# hot-wand-lite.net
KiCad netlist of a schematic drawn in EAGLE
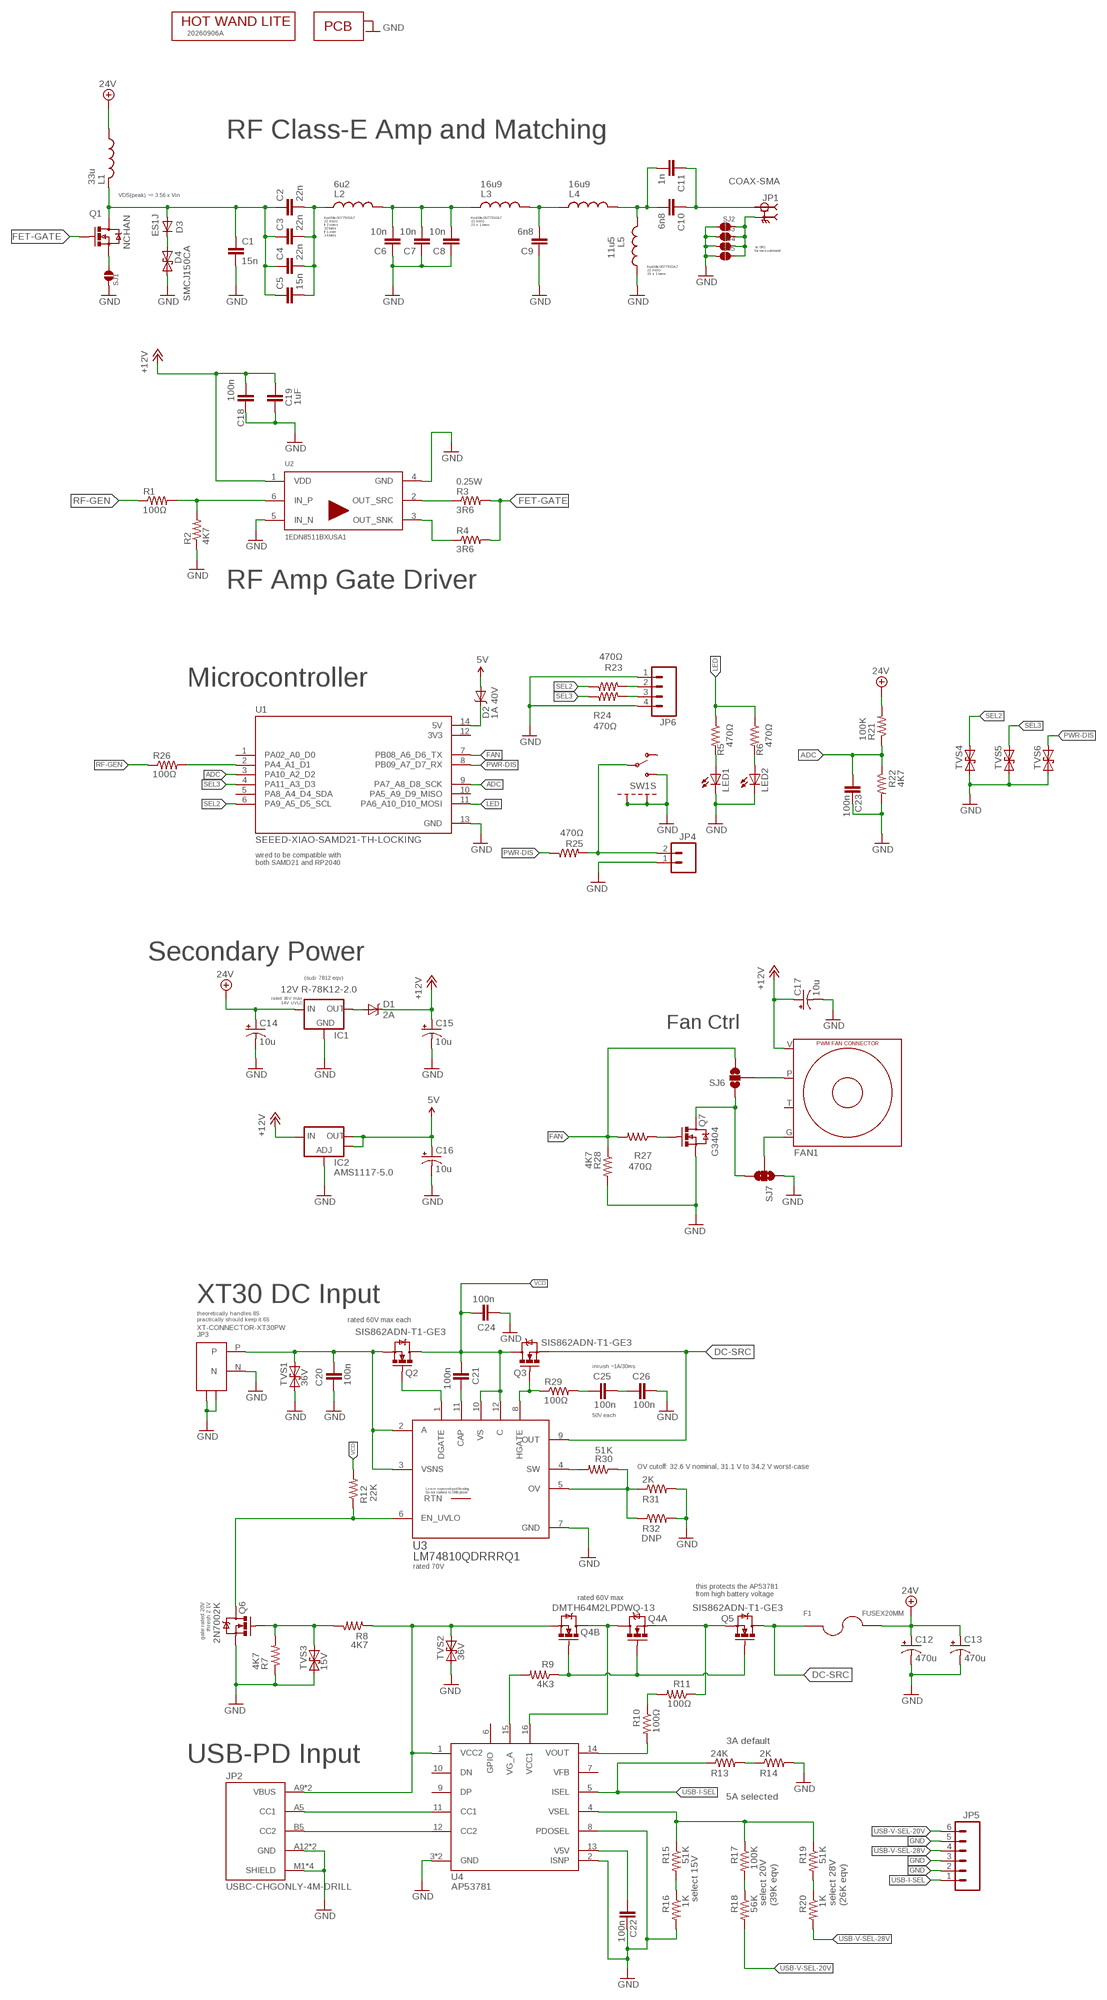
[diagram p0: schematic, sheet 1]

(export (version "E")
  (design (tool "Eeschema 10.0.6"))
  (components
    (comp (ref "C1")
      (value "15n")
      (footprint "eagle-import:1206")
      (fields (field (name "JLCPARTNUM") "C3858208") (field (name "PARTNUM") "C3216C0G2E153J160AA"))
      (libsource (lib "eagle-import") (part "CAP1206"))
    )
    (comp (ref "C2")
      (value "22n")
      (footprint "eagle-import:1206")
      (fields (field (name "JLCPARTNUM") "C3862155"))
      (libsource (lib "eagle-import") (part "CAP1206"))
    )
    (comp (ref "C3")
      (value "22n")
      (footprint "eagle-import:1206")
      (fields (field (name "JLCPARTNUM") "C3862155"))
      (libsource (lib "eagle-import") (part "CAP1206"))
    )
    (comp (ref "C4")
      (value "22n")
      (footprint "eagle-import:1206")
      (fields (field (name "JLCPARTNUM") "C3862155") (field (name "PARTNUM") "GCM31C5C2E223JX03L"))
      (libsource (lib "eagle-import") (part "CAP1206"))
    )
    (comp (ref "C5")
      (value "15n")
      (footprint "eagle-import:1206")
      (fields (field (name "JLCPARTNUM") "C3858208") (field (name "PARTNUM") "C3216C0G2E153J160AA"))
      (libsource (lib "eagle-import") (part "CAP1206"))
    )
    (comp (ref "C6")
      (value "10n")
      (footprint "eagle-import:1206")
      (fields
        (field (name "JLCPARTNUM") "C2261646;C2170837;C2175075")
        (field (name "PARTNUM") "C3216C0G2E103J115AA")
      )
      (libsource (lib "eagle-import") (part "CAP1206"))
    )
    (comp (ref "C7")
      (value "10n")
      (footprint "eagle-import:1206")
      (fields (field (name "JLCPARTNUM") "C2261646") (field (name "PARTNUM") "GRM31B5C2E103JWA1L"))
      (libsource (lib "eagle-import") (part "CAP1206"))
    )
    (comp (ref "C8")
      (value "10n")
      (footprint "eagle-import:1206")
      (fields (field (name "JLCPARTNUM") "C2261646") (field (name "PARTNUM") "GRM31B5C2E103JWA1L"))
      (libsource (lib "eagle-import") (part "CAP1206"))
    )
    (comp (ref "C9")
      (value "6n8")
      (footprint "eagle-import:1206")
      (fields (field (name "JLCPARTNUM") "C2182121") (field (name "PARTNUM") "C1206C682JCGACAUTO"))
      (libsource (lib "eagle-import") (part "CAP1206"))
    )
    (comp (ref "C10")
      (value "6n8")
      (footprint "eagle-import:1206")
      (fields (field (name "JLCPARTNUM") "C2182121") (field (name "PARTNUM") "C1206C682JCGACAUTO"))
      (libsource (lib "eagle-import") (part "CAP1206"))
    )
    (comp (ref "C11")
      (value "1n")
      (footprint "eagle-import:1206")
      (fields (field (name "JLCPARTNUM") "C3859218") (field (name "PARTNUM") "GCM31C5C3A102FX03L"))
      (libsource (lib "eagle-import") (part "CAP1206"))
    )
    (comp (ref "C12")
      (value "470u")
      (footprint "eagle-import:CPOL-RADIAL-COMBO-10MM")
      (fields (field (name "PARTNUM") "UHW1H471MPD"))
      (libsource (lib "eagle-import") (part "CAP_POLPTH5"))
    )
    (comp (ref "C13")
      (value "470u")
      (footprint "eagle-import:CPOL-RADIAL-COMBO-10MM")
      (fields (field (name "PARTNUM") "UHW1H471MPD"))
      (libsource (lib "eagle-import") (part "CAP_POLPTH5"))
    )
    (comp (ref "C14")
      (value "10u")
      (footprint "eagle-import:EIA3216-KIT")
      (fields
        (field (name "JLCPARTNUM") "C13585")
        (field (name "PARTNUM") "MLASU31LBB5106KTNA01;GRT31CR61H106KE01K")
      )
      (libsource (lib "eagle-import") (part "CAP_POL1206-KIT"))
    )
    (comp (ref "C15")
      (value "10u")
      (footprint "eagle-import:EIA3216-KIT")
      (fields (field (name "JLCPARTNUM") "C13585") (field (name "PARTNUM") "TAJA106K016TNJ;T491A106K016AT"))
      (libsource (lib "eagle-import") (part "CAP_POL1206-KIT"))
    )
    (comp (ref "C16")
      (value "10u")
      (footprint "eagle-import:EIA3216-KIT")
      (fields (field (name "JLCPARTNUM") "C13585") (field (name "PARTNUM") "TAJA106K016TNJ;T491A106K016AT"))
      (libsource (lib "eagle-import") (part "CAP_POL1206-KIT"))
    )
    (comp (ref "C17")
      (value "10u")
      (footprint "eagle-import:EIA3216-KIT")
      (fields
        (field (name "JLCPARTNUM") "C13585")
        (field (name "PARTNUM") "MLASU31LBB5106KTNA01;GRT31CR61H106KE01K")
      )
      (libsource (lib "eagle-import") (part "CAP_POL1206-KIT"))
    )
    (comp (ref "C18")
      (value "100n")
      (footprint "eagle-import:0603-CAP")
      (fields (field (name "JLCPARTNUM") "C14663"))
      (libsource (lib "eagle-import") (part "CAP0603-CAP"))
    )
    (comp (ref "C19")
      (value "1uF")
      (footprint "eagle-import:0603-CAP")
      (fields (field (name "JLCPARTNUM") "C15849"))
      (libsource (lib "eagle-import") (part "CAP0603-CAP"))
    )
    (comp (ref "C20")
      (value "100n")
      (footprint "eagle-import:0603-CAP")
      (fields (field (name "JLCPARTNUM") "C14663"))
      (libsource (lib "eagle-import") (part "CAP0603-CAP"))
    )
    (comp (ref "C21")
      (value "100n")
      (footprint "eagle-import:0603-CAP")
      (fields (field (name "JLCPARTNUM") "C14663"))
      (libsource (lib "eagle-import") (part "CAP0603-CAP"))
    )
    (comp (ref "C22")
      (value "100n")
      (footprint "eagle-import:0603-CAP")
      (fields (field (name "JLCPARTNUM") "C14663"))
      (libsource (lib "eagle-import") (part "CAP0603-CAP"))
    )
    (comp (ref "C23")
      (value "100n")
      (footprint "eagle-import:0603-CAP")
      (fields (field (name "JLCPARTNUM") "C14663"))
      (libsource (lib "eagle-import") (part "CAP0603-CAP"))
    )
    (comp (ref "C24")
      (value "100n")
      (footprint "eagle-import:0603-CAP")
      (fields (field (name "JLCPARTNUM") "C14663"))
      (libsource (lib "eagle-import") (part "CAP0603-CAP"))
    )
    (comp (ref "C25")
      (value "100n")
      (footprint "eagle-import:0603-CAP")
      (fields (field (name "JLCPARTNUM") "C14663"))
      (libsource (lib "eagle-import") (part "CAP0603-CAP"))
    )
    (comp (ref "C26")
      (value "100n")
      (footprint "eagle-import:0603-CAP")
      (fields (field (name "JLCPARTNUM") "C14663"))
      (libsource (lib "eagle-import") (part "CAP0603-CAP"))
    )
    (comp (ref "D1")
      (value "2A")
      (footprint "eagle-import:SMA-DIODE")
      (fields (field (name "JLCPARTNUM") "C698873") (field (name "PARTNUM") "VSSAF5N50;SL36A"))
      (libsource (lib "eagle-import") (part "DIODE-SCHOTTKY_"))
    )
    (comp (ref "D2")
      (value "1A 40V")
      (footprint "eagle-import:SOD123FL")
      (fields (field (name "JLCPARTNUM") "C8598"))
      (libsource (lib "eagle-import") (part "DIODE-SCHOTTKYSOD123FL"))
    )
    (comp (ref "D3")
      (value "ES1J")
      (footprint "eagle-import:SMA-DIODE")
      (fields (field (name "JLCPARTNUM") "C64879"))
      (libsource (lib "eagle-import") (part "DIODESMA"))
    )
    (comp (ref "D4")
      (value "SMCJ150CA")
      (footprint "eagle-import:SMC")
      (fields (field (name "JLCPARTNUM") "C2649864"))
      (libsource (lib "eagle-import") (part "TVSSMC"))
    )
    (comp (ref "F1")
      (value "FUSEX20MM")
      (footprint "eagle-import:FUSE_5MM")
      (fields (field (name "PARTNUM") "3518P"))
      (libsource (lib "eagle-import") (part "FUSEX20MM"))
    )
    (comp (ref "FAN1")
      (value "FAN-CONN-X4-CONN-X4")
      (footprint "eagle-import:FAN-CONN-X4")
      (fields (field (name "PARTNUM") "0470531000"))
      (libsource (lib "eagle-import") (part "FAN-CONN-X4-CONN-X4"))
    )
    (comp (ref "IC1")
      (value "12V R-78K12-2.0")
      (footprint "eagle-import:TO220-BUCK-12V")
      (fields (field (name "JLC-DNP") "1") (field (name "PARTNUM") "R-78K12-2.0"))
      (libsource (lib "eagle-import") (part "V_REG_78XX-BUCK"))
    )
    (comp (ref "IC2")
      (value "AMS1117-5.0")
      (footprint "eagle-import:SOT223")
      (fields (field (name "JLCPARTNUM") "C6187"))
      (libsource (lib "eagle-import") (part "V_REG_LM1117SOT223"))
    )
    (comp (ref "JP1")
      (value "COAX-SMA")
      (footprint "eagle-import:SAMTEC_SMA-J-P-H-ST-EM1-LGRPAD")
      (fields (field (name "MF") "Samtec") (field (name "MP") "SMA-J-P-H-ST-EM1"))
      (libsource (lib "eagle-import") (part "COAX-SMA-EDGE-LGRPAD"))
    )
    (comp (ref "JP2")
      (value "USBC-CHGONLY-4M-DRILL")
      (footprint "eagle-import:SAMESKY_UJC-H-G-SMT-2-P6-TR-DRILL")
      (fields
        (field (name "DIGIKEY_PART_NUMBER") "2223-UJC-H-G-SMT-2-P6-TRCT-ND")
        (field (name "MF") "Same Sky")
        (field (name "MP") "UJC-H-G-SMT-2-P6-TR")
        (field (name "JLC-DNP") "1")
        (field (name "PARTNUM") "UJC-H-G-SMT-P6-TR")
      )
      (libsource (lib "eagle-import") (part "USBC-CHGONLY-4M-DRILL"))
    )
    (comp (ref "JP3")
      (value "XT-CONNECTOR-XT30PW")
      (footprint "eagle-import:XT30PW")
      (fields (field (name "JLC-DNP") "1") (field (name "PARTNUM") "XT30PW-M"))
      (libsource (lib "eagle-import") (part "XT-CONNECTOR-XT30PW"))
    )
    (comp (ref "JP4")
      (value "M02PTH3")
      (footprint "eagle-import:1X02_LONGPADS")
      (libsource (lib "eagle-import") (part "M02PTH3"))
    )
    (comp (ref "JP5")
      (value "M06LOCK")
      (footprint "eagle-import:1X06_LOCK")
      (libsource (lib "eagle-import") (part "M06LOCK"))
    )
    (comp (ref "JP6")
      (value "M04LOCK")
      (footprint "eagle-import:1X04_LOCK")
      (libsource (lib "eagle-import") (part "M04LOCK"))
    )
    (comp (ref "L1")
      (value "33u")
      (footprint "eagle-import:IND_SRP1265A")
      (fields
        (field (name "JLCPARTNUM") "C2453886")
        (field (name "PARTNUM") "PA4343.333NLT;SRP1265A-330M;SRP1265CC-330M")
      )
      (libsource (lib "eagle-import") (part "INDUCTOR-SRP1265A"))
    )
    (comp (ref "L2")
      (value "6u2")
      (footprint "eagle-import:IND-KOOLMU-2W")
      (libsource (lib "eagle-import") (part "INDUCTOR-KOOLMU-2W"))
    )
    (comp (ref "L3")
      (value "16u9")
      (footprint "eagle-import:IND-KOOLMU")
      (libsource (lib "eagle-import") (part "INDUCTOR-KOOLMU"))
    )
    (comp (ref "L4")
      (value "16u9")
      (footprint "eagle-import:IND-KOOLMU")
      (libsource (lib "eagle-import") (part "INDUCTOR-KOOLMU"))
    )
    (comp (ref "L5")
      (value "11u5")
      (footprint "eagle-import:IND-KOOLMU")
      (libsource (lib "eagle-import") (part "INDUCTOR-KOOLMU"))
    )
    (comp (ref "LED1")
      (value "LED")
      (footprint "eagle-import:LED_LTST-S220KRKT")
      (fields (field (name "JLCPARTNUM") "C284935") (field (name "PARTNUM") "LTST-S220KRKT"))
      (libsource (lib "eagle-import") (part "LED-LTST-S220KRKT"))
    )
    (comp (ref "LED2")
      (value "LED")
      (footprint "eagle-import:LED-0603")
      (fields (field (name "JLC-DNP") "1"))
      (libsource (lib "eagle-import") (part "LED0603"))
    )
    (comp (ref "PCB1")
      (value "PCB-OUTLINE")
      (footprint "eagle-import:PCB-OUTLINE")
      (fields (field (name "JLC-DNP") "1"))
      (libsource (lib "eagle-import") (part "PCB-OUTLINE"))
    )
    (comp (ref "PCB2")
      (value "PCB-ART-VER-LITE")
      (footprint "eagle-import:PCB-ART-VERSION-LITE")
      (libsource (lib "eagle-import") (part "PCB-ART-VER-LITE"))
    )
    (comp (ref "Q1")
      (value "NCHAN")
      (footprint "eagle-import:TO247-COMBO")
      (libsource (lib "eagle-import") (part "MOSFET-NCHANNEL-TO247-COMBO"))
    )
    (comp (ref "Q2")
      (value "SIS862ADN-T1-GE3")
      (footprint "eagle-import:POWERPAK-1212-8")
      (fields (field (name "PARTNUM") "SIS862ADN-T1-GE3"))
      (libsource (lib "eagle-import") (part "MOSFET-NCHANNEL-POWERPAK1212-8"))
    )
    (comp (ref "Q3")
      (value "SIS862ADN-T1-GE3")
      (footprint "eagle-import:POWERPAK-1212-8")
      (fields (field (name "PARTNUM") "SIS862ADN-T1-GE3"))
      (libsource (lib "eagle-import") (part "MOSFET-NCHANNEL-POWERPAK1212-8"))
    )
    (comp (ref "Q4")
      (value "DMTH64M2LPDWQ-13")
      (footprint "eagle-import:POWERPAK-SO8-X2")
      (fields (field (name "JLC-DNP") "1") (field (name "PARTNUM") "DMTH64M2LPDWQ-13"))
      (libsource (lib "eagle-import") (part "MOSFET-NCHAN-X2-PPSO8X2"))
    )
    (comp (ref "Q5")
      (value "SIS862ADN-T1-GE3")
      (footprint "eagle-import:POWERPAK-1212-8")
      (fields (field (name "JLC-DNP") "1") (field (name "PARTNUM") "SIS862ADN-T1-GE3"))
      (libsource (lib "eagle-import") (part "MOSFET-NCHANNEL-POWERPAK1212-8"))
    )
    (comp (ref "Q6")
      (value "2N7002K")
      (footprint "eagle-import:SOT23-3")
      (fields
        (field (name "JLCPARTNUM") "C14498;C547263;C5224211;C54347659")
        (field (name "PARTNUM") "2N7002K;SSM3K388R,LF;Si2318CDS-T1-GE3;PMV60ENEAR")
      )
      (libsource (lib "eagle-import") (part "MOSFET-NCHANNELSMD"))
    )
    (comp (ref "Q7")
      (value "G3404")
      (footprint "eagle-import:SOT23-3")
      (fields
        (field (name "JLCPARTNUM") "C14498;C547263;C96615")
        (field (name "PARTNUM") "G3404;MMFTN3404A;PJA3404A;Si2318CDS-T1-GE3;PMV60ENEAR")
      )
      (libsource (lib "eagle-import") (part "MOSFET-NCHANNELSMD"))
    )
    (comp (ref "R1")
      (value "100Ω")
      (footprint "eagle-import:0805")
      (fields (field (name "JLCPARTNUM") "C441975"))
      (libsource (lib "eagle-import") (part "RESISTOR0805-RES"))
    )
    (comp (ref "R2")
      (value "4K7")
      (footprint "eagle-import:0603-RES")
      (fields (field (name "JLCPARTNUM") "C23162"))
      (libsource (lib "eagle-import") (part "RESISTOR0603-RES"))
    )
    (comp (ref "R3")
      (value "3R6")
      (footprint "eagle-import:0603-RES")
      (fields (field (name "JLCPARTNUM") "C445783"))
      (libsource (lib "eagle-import") (part "RESISTOR0603-RES"))
    )
    (comp (ref "R4")
      (value "3R6")
      (footprint "eagle-import:0603-RES")
      (fields (field (name "JLCPARTNUM") "C445783"))
      (libsource (lib "eagle-import") (part "RESISTOR0603-RES"))
    )
    (comp (ref "R5")
      (value "470Ω")
      (footprint "eagle-import:0603-RES")
      (fields (field (name "JLCPARTNUM") "C23179"))
      (libsource (lib "eagle-import") (part "RESISTOR0603-RES"))
    )
    (comp (ref "R6")
      (value "470Ω")
      (footprint "eagle-import:0603-RES")
      (fields (field (name "JLCPARTNUM") "C23179"))
      (libsource (lib "eagle-import") (part "RESISTOR0603-RES"))
    )
    (comp (ref "R7")
      (value "4K7")
      (footprint "eagle-import:0603-RES")
      (fields (field (name "JLCPARTNUM") "C23162"))
      (libsource (lib "eagle-import") (part "RESISTOR0603-RES"))
    )
    (comp (ref "R8")
      (value "4K7")
      (footprint "eagle-import:0603-RES")
      (fields (field (name "JLCPARTNUM") "C23162"))
      (libsource (lib "eagle-import") (part "RESISTOR0603-RES"))
    )
    (comp (ref "R9")
      (value "4K3")
      (footprint "eagle-import:0603-RES")
      (fields (field (name "JLCPARTNUM") "C23159"))
      (libsource (lib "eagle-import") (part "RESISTOR0603-RES"))
    )
    (comp (ref "R10")
      (value "100Ω")
      (footprint "eagle-import:0805")
      (fields (field (name "JLCPARTNUM") "C441975"))
      (libsource (lib "eagle-import") (part "RESISTOR0805-RES"))
    )
    (comp (ref "R11")
      (value "100Ω")
      (footprint "eagle-import:0805")
      (fields (field (name "JLCPARTNUM") "C441975"))
      (libsource (lib "eagle-import") (part "RESISTOR0805-RES"))
    )
    (comp (ref "R12")
      (value "22K")
      (footprint "eagle-import:0603-RES")
      (fields (field (name "JLCPARTNUM") "C31850"))
      (libsource (lib "eagle-import") (part "RESISTOR0603-RES"))
    )
    (comp (ref "R13")
      (value "24K")
      (footprint "eagle-import:0603-RES")
      (fields (field (name "JLCPARTNUM") "C23352"))
      (libsource (lib "eagle-import") (part "RESISTOR0603-RES"))
    )
    (comp (ref "R14")
      (value "2K")
      (footprint "eagle-import:0603-RES")
      (fields (field (name "JLCPARTNUM") "C22975"))
      (libsource (lib "eagle-import") (part "RESISTOR0603-RES"))
    )
    (comp (ref "R15")
      (value "51K")
      (footprint "eagle-import:0603-RES")
      (fields (field (name "JLCPARTNUM") "C23196"))
      (libsource (lib "eagle-import") (part "RESISTOR0603-RES"))
    )
    (comp (ref "R16")
      (value "1K")
      (footprint "eagle-import:0603-RES")
      (fields (field (name "JLCPARTNUM") "C21190"))
      (libsource (lib "eagle-import") (part "RESISTOR0603-RES"))
    )
    (comp (ref "R17")
      (value "100K")
      (footprint "eagle-import:0603-RES")
      (fields (field (name "JLCPARTNUM") "C25803"))
      (libsource (lib "eagle-import") (part "RESISTOR0603-RES"))
    )
    (comp (ref "R18")
      (value "56K")
      (footprint "eagle-import:0603-RES")
      (fields (field (name "JLCPARTNUM") "C23206"))
      (libsource (lib "eagle-import") (part "RESISTOR0603-RES"))
    )
    (comp (ref "R19")
      (value "51K")
      (footprint "eagle-import:0603-RES")
      (fields (field (name "JLCPARTNUM") "C23196"))
      (libsource (lib "eagle-import") (part "RESISTOR0603-RES"))
    )
    (comp (ref "R20")
      (value "1K")
      (footprint "eagle-import:0603-RES")
      (fields (field (name "JLCPARTNUM") "C21190"))
      (libsource (lib "eagle-import") (part "RESISTOR0603-RES"))
    )
    (comp (ref "R21")
      (value "100K")
      (footprint "eagle-import:0603-RES")
      (fields (field (name "JLCPARTNUM") "C25803"))
      (libsource (lib "eagle-import") (part "RESISTOR0603-RES"))
    )
    (comp (ref "R22")
      (value "4K7")
      (footprint "eagle-import:0603-RES")
      (fields (field (name "JLCPARTNUM") "C23162"))
      (libsource (lib "eagle-import") (part "RESISTOR0603-RES"))
    )
    (comp (ref "R23")
      (value "470Ω")
      (footprint "eagle-import:0603-RES")
      (fields (field (name "JLCPARTNUM") "C23179"))
      (libsource (lib "eagle-import") (part "RESISTOR0603-RES"))
    )
    (comp (ref "R24")
      (value "470Ω")
      (footprint "eagle-import:0603-RES")
      (fields (field (name "JLCPARTNUM") "C23179"))
      (libsource (lib "eagle-import") (part "RESISTOR0603-RES"))
    )
    (comp (ref "R25")
      (value "470Ω")
      (footprint "eagle-import:0603-RES")
      (fields (field (name "JLCPARTNUM") "C23179"))
      (libsource (lib "eagle-import") (part "RESISTOR0603-RES"))
    )
    (comp (ref "R26")
      (value "100Ω")
      (footprint "eagle-import:0805")
      (fields (field (name "JLCPARTNUM") "C441975"))
      (libsource (lib "eagle-import") (part "RESISTOR0805-RES"))
    )
    (comp (ref "R27")
      (value "470Ω")
      (footprint "eagle-import:0603-RES")
      (fields (field (name "JLCPARTNUM") "C23179"))
      (libsource (lib "eagle-import") (part "RESISTOR0603-RES"))
    )
    (comp (ref "R28")
      (value "4K7")
      (footprint "eagle-import:0603-RES")
      (fields (field (name "JLCPARTNUM") "C23162"))
      (libsource (lib "eagle-import") (part "RESISTOR0603-RES"))
    )
    (comp (ref "R29")
      (value "100Ω")
      (footprint "eagle-import:0805")
      (fields (field (name "JLCPARTNUM") "C441975"))
      (libsource (lib "eagle-import") (part "RESISTOR0805-RES"))
    )
    (comp (ref "R30")
      (value "51K")
      (footprint "eagle-import:0603-RES")
      (fields (field (name "JLCPARTNUM") "C23196"))
      (libsource (lib "eagle-import") (part "RESISTOR0603-RES"))
    )
    (comp (ref "R31")
      (value "2K")
      (footprint "eagle-import:0603-RES")
      (fields (field (name "JLCPARTNUM") "C22975"))
      (libsource (lib "eagle-import") (part "RESISTOR0603-RES"))
    )
    (comp (ref "R32")
      (value "DNP")
      (footprint "eagle-import:0603-RES")
      (fields (field (name "DNP") "1"))
      (libsource (lib "eagle-import") (part "RESISTOR0603-RES"))
    )
    (comp (ref "SJ1")
      (value "SJ-SMALL-1206-SJ")
      (footprint "eagle-import:1206-SJ")
      (libsource (lib "eagle-import") (part "SJ-SMALL-1206-SJ"))
    )
    (comp (ref "SJ2")
      (value "SJ-SMALL-1206-SJ")
      (footprint "eagle-import:1206-SJ")
      (libsource (lib "eagle-import") (part "SJ-SMALL-1206-SJ"))
    )
    (comp (ref "SJ3")
      (value "SJ-SMALL-1206-SJ")
      (footprint "eagle-import:1206-SJ")
      (libsource (lib "eagle-import") (part "SJ-SMALL-1206-SJ"))
    )
    (comp (ref "SJ4")
      (value "SJ-SMALL-1206-SJ")
      (footprint "eagle-import:1206-SJ")
      (libsource (lib "eagle-import") (part "SJ-SMALL-1206-SJ"))
    )
    (comp (ref "SJ5")
      (value "SJ-SMALL-1206-SJ")
      (footprint "eagle-import:1206-SJ")
      (libsource (lib "eagle-import") (part "SJ-SMALL-1206-SJ"))
    )
    (comp (ref "SJ6")
      (value "SOLDERJUMPER_2WAYS")
      (footprint "eagle-import:SJ_3")
      (libsource (lib "eagle-import") (part "SOLDERJUMPER_2WAYS"))
    )
    (comp (ref "SJ7")
      (value "SOLDERJUMPER_2WAYS")
      (footprint "eagle-import:SJ_3")
      (libsource (lib "eagle-import") (part "SOLDERJUMPER_2WAYS"))
    )
    (comp (ref "SW1")
      (value "SWITCH-SPDT-2MNT-SLW-864574-5A-RA-N-D")
      (footprint "eagle-import:SWITCH-SLW-864574-5A-RA-N-D")
      (fields (field (name "JLC-DNP") "1") (field (name "PARTNUM") "SLW-864574-5A-RA-N-D"))
      (libsource (lib "eagle-import") (part "SWITCH-SPDT-2MNT-SLW-864574-5A-RA-N-D"))
    )
    (comp (ref "TVS1")
      (value "36V")
      (footprint "eagle-import:SMA")
      (fields (field (name "JLCPARTNUM") "C134984") (field (name "PARTNUM") "SMAJ36CA"))
      (libsource (lib "eagle-import") (part "TVSSMA"))
    )
    (comp (ref "TVS2")
      (value "36V")
      (footprint "eagle-import:SMA")
      (fields (field (name "JLCPARTNUM") "C134984") (field (name "PARTNUM") "SMAJ36CA"))
      (libsource (lib "eagle-import") (part "TVSSMA"))
    )
    (comp (ref "TVS3")
      (value "15V")
      (footprint "eagle-import:SOD-323")
      (fields
        (field (name "JLCPARTNUM") "C2987151")
        (field (name "PARTNUM") "SD15C-01FTG;CDSOD323-T15SC;TSD15CDYFR")
      )
      (libsource (lib "eagle-import") (part "TVSSOD-323"))
    )
    (comp (ref "TVS4")
      (value "TVSSOD323-R")
      (footprint "eagle-import:SOD323-R")
      (fields (field (name "JLCPARTNUM") "C840638"))
      (libsource (lib "eagle-import") (part "TVSSOD323-R"))
    )
    (comp (ref "TVS5")
      (value "TVSSOD323-R")
      (footprint "eagle-import:SOD323-R")
      (fields (field (name "JLCPARTNUM") "C840638"))
      (libsource (lib "eagle-import") (part "TVSSOD323-R"))
    )
    (comp (ref "TVS6")
      (value "TVSSOD323-R")
      (footprint "eagle-import:SOD323-R")
      (fields (field (name "JLCPARTNUM") "C840638"))
      (libsource (lib "eagle-import") (part "TVSSOD323-R"))
    )
    (comp (ref "U1")
      (value "SEEED-XIAO-SAMD21-TH-LOCKING")
      (footprint "eagle-import:MODULE_102010388_LOCKING")
      (fields (field (name "MF") "seeed technology limited") (field (name "MP") "102010388"))
      (libsource (lib "eagle-import") (part "SEEED-XIAO-SAMD21-TH-LOCKING"))
    )
    (comp (ref "U2")
      (value "1EDN8511BXUSA1")
      (footprint "eagle-import:SOT95P280X145-6N-7-V")
      (fields (field (name "JLCPARTNUM") "C3655509"))
      (libsource (lib "eagle-import") (part "1EDN8511B"))
    )
    (comp (ref "U3")
      (value "LM74810QDRRRQ1")
      (footprint "eagle-import:DRR0012E-MFG")
      (fields
        (field (name "JLCPARTNUM") "C3215601")
        (field (name "COPYRIGHT") "Copyright (C) 2026 Ultra Librarian. All rights reserved.")
      )
      (libsource (lib "eagle-import") (part "LM74810QDRRRQ1"))
    )
    (comp (ref "U4")
      (value "AP53781")
      (footprint "eagle-import:QFN3030-16")
      (fields (field (name "JLCPARTNUM") "C52730979"))
      (libsource (lib "eagle-import") (part "AP53781-QFN3030-16"))
    )
  )
  (nets
    (net (code "1") (name "+12V") (class "Default")
      (node (ref "C15") (pin "A") (pinfunction "+_A") (pintype "passive"))
      (node (ref "C17") (pin "A") (pinfunction "+_A") (pintype "passive"))
      (node (ref "C18") (pin "2") (pinfunction "2_2") (pintype "passive"))
      (node (ref "C19") (pin "2") (pinfunction "2_2") (pintype "passive"))
      (node (ref "D1") (pin "C") (pinfunction "C_C") (pintype "passive"))
      (node (ref "FAN1") (pin "V") (pinfunction "V_V") (pintype "bidirectional"))
      (node (ref "IC2") (pin "3") (pinfunction "IN_3") (pintype "input"))
      (node (ref "U2") (pin "1") (pinfunction "VDD_1") (pintype "power_in"))
    )
    (net (code "2") (name "/3V3") (class "Default")
      (node (ref "U1") (pin "12") (pinfunction "3V3_12") (pintype "power_in"))
    )
    (net (code "3") (name "5V") (class "Default")
      (node (ref "C16") (pin "A") (pinfunction "+_A") (pintype "passive"))
      (node (ref "D2") (pin "A") (pinfunction "A_A") (pintype "passive"))
      (node (ref "IC2") (pin "2") (pinfunction "OUT_2") (pintype "output"))
      (node (ref "IC2") (pin "4") (pinfunction "OUT_4") (pintype "output"))
    )
    (net (code "4") (name "24V") (class "Default")
      (node (ref "C12") (pin "1") (pinfunction "+_1") (pintype "passive"))
      (node (ref "C12") (pin "1B") (pinfunction "+_1B") (pintype "passive"))
      (node (ref "C13") (pin "1") (pinfunction "+_1") (pintype "passive"))
      (node (ref "C13") (pin "1B") (pinfunction "+_1B") (pintype "passive"))
      (node (ref "C14") (pin "A") (pinfunction "+_A") (pintype "passive"))
      (node (ref "F1") (pin "3") (pinfunction "2_3") (pintype "bidirectional"))
      (node (ref "F1") (pin "4") (pinfunction "2_4") (pintype "bidirectional"))
      (node (ref "IC1") (pin "1") (pinfunction "IN_1") (pintype "input"))
      (node (ref "L1") (pin "1") (pinfunction "1_1") (pintype "passive"))
      (node (ref "R21") (pin "2") (pinfunction "2_2") (pintype "passive"))
    )
    (net (code "5") (name "ADC") (class "Default")
      (node (ref "C23") (pin "2") (pinfunction "2_2") (pintype "passive"))
      (node (ref "R21") (pin "1") (pinfunction "1_1") (pintype "passive"))
      (node (ref "R22") (pin "1") (pinfunction "1_1") (pintype "passive"))
      (node (ref "U1") (pin "3") (pinfunction "PA10_A2_D2_3") (pintype "bidirectional"))
      (node (ref "U1") (pin "9") (pinfunction "PA7_A8_D8_SCK_9") (pintype "bidirectional"))
    )
    (net (code "6") (name "DC-SRC") (class "Default")
      (node (ref "F1") (pin "1") (pinfunction "1_1") (pintype "bidirectional"))
      (node (ref "F1") (pin "2") (pinfunction "1_2") (pintype "bidirectional"))
      (node (ref "Q3") (pin "1") (pinfunction "S_1") (pintype "passive"))
      (node (ref "Q3") (pin "2") (pinfunction "S_2") (pintype "passive"))
      (node (ref "Q3") (pin "3") (pinfunction "S_3") (pintype "passive"))
      (node (ref "Q5") (pin "5") (pinfunction "D_5") (pintype "passive"))
      (node (ref "Q5") (pin "6") (pinfunction "D_6") (pintype "passive"))
      (node (ref "Q5") (pin "7") (pinfunction "D_7") (pintype "passive"))
      (node (ref "Q5") (pin "8") (pinfunction "D_8") (pintype "passive"))
      (node (ref "Q5") (pin "9") (pinfunction "D_9") (pintype "passive"))
      (node (ref "U3") (pin "9") (pinfunction "OUT_9") (pintype "passive"))
    )
    (net (code "7") (name "FAN") (class "Default")
      (node (ref "R27") (pin "2") (pinfunction "2_2") (pintype "passive"))
      (node (ref "R28") (pin "1") (pinfunction "1_1") (pintype "passive"))
      (node (ref "SJ6") (pin "3") (pinfunction "3_3") (pintype "passive"))
      (node (ref "U1") (pin "7") (pinfunction "PB08_A6_D6_TX_7") (pintype "bidirectional"))
    )
    (net (code "8") (name "FET-GATE") (class "Default")
      (node (ref "Q1") (pin "1") (pinfunction "G_1") (pintype "passive"))
      (node (ref "Q1") (pin "1B") (pinfunction "G_1B") (pintype "passive"))
      (node (ref "R3") (pin "2") (pinfunction "2_2") (pintype "passive"))
      (node (ref "R4") (pin "2") (pinfunction "2_2") (pintype "passive"))
    )
    (net (code "9") (name "GND") (class "Default")
      (node (ref "C1") (pin "2") (pinfunction "2_2") (pintype "passive"))
      (node (ref "C12") (pin "2") (pinfunction "-_2") (pintype "passive"))
      (node (ref "C12") (pin "2B") (pinfunction "-_2B") (pintype "passive"))
      (node (ref "C13") (pin "2") (pinfunction "-_2") (pintype "passive"))
      (node (ref "C13") (pin "2B") (pinfunction "-_2B") (pintype "passive"))
      (node (ref "C14") (pin "C") (pinfunction "-_C") (pintype "passive"))
      (node (ref "C15") (pin "C") (pinfunction "-_C") (pintype "passive"))
      (node (ref "C16") (pin "C") (pinfunction "-_C") (pintype "passive"))
      (node (ref "C17") (pin "C") (pinfunction "-_C") (pintype "passive"))
      (node (ref "C18") (pin "1") (pinfunction "1_1") (pintype "passive"))
      (node (ref "C19") (pin "1") (pinfunction "1_1") (pintype "passive"))
      (node (ref "C20") (pin "2") (pinfunction "2_2") (pintype "passive"))
      (node (ref "C22") (pin "1") (pinfunction "1_1") (pintype "passive"))
      (node (ref "C23") (pin "1") (pinfunction "1_1") (pintype "passive"))
      (node (ref "C24") (pin "2") (pinfunction "2_2") (pintype "passive"))
      (node (ref "C26") (pin "1") (pinfunction "1_1") (pintype "passive"))
      (node (ref "C6") (pin "1") (pinfunction "1_1") (pintype "passive"))
      (node (ref "C7") (pin "1") (pinfunction "1_1") (pintype "passive"))
      (node (ref "C8") (pin "1") (pinfunction "1_1") (pintype "passive"))
      (node (ref "C9") (pin "1") (pinfunction "1_1") (pintype "passive"))
      (node (ref "D4") (pin "A") (pinfunction "1_A") (pintype "passive"))
      (node (ref "IC1") (pin "2") (pinfunction "GND_2") (pintype "input"))
      (node (ref "IC2") (pin "1") (pinfunction "ADJ_1") (pintype "input"))
      (node (ref "JP2") (pin "A12") (pinfunction "GND_A12") (pintype "passive"))
      (node (ref "JP2") (pin "B12") (pinfunction "GND_B12") (pintype "passive"))
      (node (ref "JP2") (pin "M1") (pinfunction "SHIELD_M1") (pintype "passive"))
      (node (ref "JP2") (pin "M2") (pinfunction "SHIELD_M2") (pintype "passive"))
      (node (ref "JP2") (pin "M3") (pinfunction "SHIELD_M3") (pintype "passive"))
      (node (ref "JP2") (pin "M4") (pinfunction "SHIELD_M4") (pintype "passive"))
      (node (ref "JP3") (pin "M1") (pinfunction "M1_M1") (pintype "bidirectional"))
      (node (ref "JP3") (pin "M2") (pinfunction "M2_M2") (pintype "bidirectional"))
      (node (ref "JP3") (pin "N") (pinfunction "N_N") (pintype "bidirectional"))
      (node (ref "JP4") (pin "1") (pinfunction "1_1") (pintype "passive"))
      (node (ref "JP5") (pin "2") (pinfunction "2_2") (pintype "passive"))
      (node (ref "JP5") (pin "3") (pinfunction "3_3") (pintype "passive"))
      (node (ref "JP5") (pin "5") (pinfunction "5_5") (pintype "passive"))
      (node (ref "JP6") (pin "1") (pinfunction "1_1") (pintype "passive"))
      (node (ref "JP6") (pin "4") (pinfunction "4_4") (pintype "passive"))
      (node (ref "L5") (pin "1") (pinfunction "1_1") (pintype "passive"))
      (node (ref "LED1") (pin "C") (pinfunction "C_C") (pintype "passive"))
      (node (ref "LED2") (pin "C") (pinfunction "C_C") (pintype "passive"))
      (node (ref "PCB1") (pin "1") (pinfunction "1_1") (pintype "bidirectional"))
      (node (ref "PCB1") (pin "2") (pinfunction "1_2") (pintype "bidirectional"))
      (node (ref "PCB1") (pin "3") (pinfunction "1_3") (pintype "bidirectional"))
      (node (ref "PCB1") (pin "4") (pinfunction "1_4") (pintype "bidirectional"))
      (node (ref "Q6") (pin "2") (pinfunction "S_2") (pintype "passive"))
      (node (ref "Q7") (pin "2") (pinfunction "S_2") (pintype "passive"))
      (node (ref "R14") (pin "2") (pinfunction "2_2") (pintype "passive"))
      (node (ref "R16") (pin "2") (pinfunction "2_2") (pintype "passive"))
      (node (ref "R2") (pin "1") (pinfunction "1_1") (pintype "passive"))
      (node (ref "R22") (pin "2") (pinfunction "2_2") (pintype "passive"))
      (node (ref "R28") (pin "2") (pinfunction "2_2") (pintype "passive"))
      (node (ref "R31") (pin "2") (pinfunction "2_2") (pintype "passive"))
      (node (ref "R32") (pin "2") (pinfunction "2_2") (pintype "passive"))
      (node (ref "R7") (pin "1") (pinfunction "1_1") (pintype "passive"))
      (node (ref "SJ1") (pin "1") (pinfunction "1_1") (pintype "bidirectional"))
      (node (ref "SJ2") (pin "2") (pinfunction "2_2") (pintype "bidirectional"))
      (node (ref "SJ3") (pin "2") (pinfunction "2_2") (pintype "bidirectional"))
      (node (ref "SJ4") (pin "2") (pinfunction "2_2") (pintype "bidirectional"))
      (node (ref "SJ5") (pin "2") (pinfunction "2_2") (pintype "bidirectional"))
      (node (ref "SJ7") (pin "1") (pinfunction "1_1") (pintype "passive"))
      (node (ref "SW1") (pin "M1") (pinfunction "MNT1_M1") (pintype "bidirectional"))
      (node (ref "SW1") (pin "M2") (pinfunction "MNT2_M2") (pintype "bidirectional"))
      (node (ref "SW1") (pin "R") (pinfunction "S_R") (pintype "passive"))
      (node (ref "TVS1") (pin "A") (pinfunction "1_A") (pintype "passive"))
      (node (ref "TVS2") (pin "A") (pinfunction "1_A") (pintype "passive"))
      (node (ref "TVS3") (pin "2") (pinfunction "1_2") (pintype "passive"))
      (node (ref "TVS4") (pin "A") (pinfunction "1_A") (pintype "passive"))
      (node (ref "TVS5") (pin "A") (pinfunction "1_A") (pintype "passive"))
      (node (ref "TVS6") (pin "A") (pinfunction "1_A") (pintype "passive"))
      (node (ref "U1") (pin "13") (pinfunction "GND_13") (pintype "power_in"))
      (node (ref "U2") (pin "4") (pinfunction "GND_4") (pintype "power_in"))
      (node (ref "U2") (pin "5") (pinfunction "IN_N_5") (pintype "input"))
      (node (ref "U3") (pin "7") (pinfunction "GND_7") (pintype "power_in"))
      (node (ref "U4") (pin "2") (pinfunction "ISNP_2") (pintype "bidirectional"))
      (node (ref "U4") (pin "3") (pinfunction "GND_3") (pintype "bidirectional"))
      (node (ref "U4") (pin "8") (pinfunction "PDOSEL_8") (pintype "bidirectional"))
      (node (ref "U4") (pin "EXP") (pinfunction "GND_EXP") (pintype "bidirectional"))
    )
    (net (code "10") (name "LED") (class "Default")
      (node (ref "R5") (pin "1") (pinfunction "1_1") (pintype "passive"))
      (node (ref "R6") (pin "1") (pinfunction "1_1") (pintype "passive"))
      (node (ref "U1") (pin "11") (pinfunction "PA6_A10_D10_MOSI_11") (pintype "bidirectional"))
    )
    (net (code "11") (name "Net-(C2-Pad2)") (class "Default")
      (node (ref "C2") (pin "2") (pinfunction "2_2") (pintype "passive"))
      (node (ref "C3") (pin "2") (pinfunction "2_2") (pintype "passive"))
      (node (ref "C4") (pin "2") (pinfunction "2_2") (pintype "passive"))
      (node (ref "C5") (pin "2") (pinfunction "2_2") (pintype "passive"))
      (node (ref "L2") (pin "1A") (pinfunction "1_1A") (pintype "passive"))
      (node (ref "L2") (pin "1B") (pinfunction "1_1B") (pintype "passive"))
      (node (ref "L2") (pin "1C") (pinfunction "1_1C") (pintype "passive"))
      (node (ref "L2") (pin "1D") (pinfunction "1_1D") (pintype "passive"))
    )
    (net (code "12") (name "Net-(C6-Pad2)") (class "Default")
      (node (ref "C6") (pin "2") (pinfunction "2_2") (pintype "passive"))
      (node (ref "C7") (pin "2") (pinfunction "2_2") (pintype "passive"))
      (node (ref "C8") (pin "2") (pinfunction "2_2") (pintype "passive"))
      (node (ref "L2") (pin "2A") (pinfunction "2_2A") (pintype "passive"))
      (node (ref "L2") (pin "2B") (pinfunction "2_2B") (pintype "passive"))
      (node (ref "L2") (pin "2C") (pinfunction "2_2C") (pintype "passive"))
      (node (ref "L2") (pin "2D") (pinfunction "2_2D") (pintype "passive"))
      (node (ref "L3") (pin "1") (pinfunction "1_1") (pintype "passive"))
    )
    (net (code "13") (name "Net-(C9-Pad2)") (class "Default")
      (node (ref "C9") (pin "2") (pinfunction "2_2") (pintype "passive"))
      (node (ref "L3") (pin "2") (pinfunction "2_2") (pintype "passive"))
      (node (ref "L4") (pin "1") (pinfunction "1_1") (pintype "passive"))
    )
    (net (code "14") (name "Net-(C10-Pad1)") (class "Default")
      (node (ref "C10") (pin "1") (pinfunction "1_1") (pintype "passive"))
      (node (ref "C11") (pin "1") (pinfunction "1_1") (pintype "passive"))
      (node (ref "JP1") (pin "1") (pinfunction "1_1") (pintype "passive"))
    )
    (net (code "15") (name "Net-(C10-Pad2)") (class "Default")
      (node (ref "C10") (pin "2") (pinfunction "2_2") (pintype "passive"))
      (node (ref "C11") (pin "2") (pinfunction "2_2") (pintype "passive"))
      (node (ref "L4") (pin "2") (pinfunction "2_2") (pintype "passive"))
      (node (ref "L5") (pin "2") (pinfunction "2_2") (pintype "passive"))
    )
    (net (code "16") (name "Net-(C25-Pad1)") (class "Default")
      (node (ref "C25") (pin "1") (pinfunction "1_1") (pintype "passive"))
      (node (ref "C26") (pin "2") (pinfunction "2_2") (pintype "passive"))
    )
    (net (code "17") (name "Net-(C25-Pad2)") (class "Default")
      (node (ref "C25") (pin "2") (pinfunction "2_2") (pintype "passive"))
      (node (ref "R29") (pin "2") (pinfunction "2_2") (pintype "passive"))
    )
    (net (code "18") (name "Net-(D4-2)") (class "Default")
      (node (ref "D3") (pin "C") (pinfunction "C_C") (pintype "passive"))
      (node (ref "D4") (pin "C") (pinfunction "2_C") (pintype "passive"))
    )
    (net (code "19") (name "Net-(FAN1-PadG)") (class "Default")
      (node (ref "FAN1") (pin "G") (pinfunction "G_G") (pintype "bidirectional"))
      (node (ref "SJ7") (pin "2") (pinfunction "2_2") (pintype "passive"))
    )
    (net (code "20") (name "Net-(FAN1-PadP)") (class "Default")
      (node (ref "FAN1") (pin "P") (pinfunction "P_P") (pintype "bidirectional"))
      (node (ref "SJ6") (pin "2") (pinfunction "2_2") (pintype "passive"))
    )
    (net (code "21") (name "Net-(IC1-OUT)") (class "Default")
      (node (ref "D1") (pin "A") (pinfunction "A_A") (pintype "passive"))
      (node (ref "IC1") (pin "3") (pinfunction "OUT_3") (pintype "output"))
    )
    (net (code "22") (name "Net-(JP1-2-Pad2_1)") (class "Default")
      (node (ref "JP1") (pin "2_1") (pinfunction "2_2_1") (pintype "passive"))
      (node (ref "JP1") (pin "2_2") (pinfunction "2_2_2") (pintype "passive"))
      (node (ref "JP1") (pin "3_1") (pinfunction "2_3_1") (pintype "passive"))
      (node (ref "JP1") (pin "3_2") (pinfunction "2_3_2") (pintype "passive"))
      (node (ref "SJ2") (pin "1") (pinfunction "1_1") (pintype "bidirectional"))
      (node (ref "SJ3") (pin "1") (pinfunction "1_1") (pintype "bidirectional"))
      (node (ref "SJ4") (pin "1") (pinfunction "1_1") (pintype "bidirectional"))
      (node (ref "SJ5") (pin "1") (pinfunction "1_1") (pintype "bidirectional"))
    )
    (net (code "23") (name "Net-(JP2-CC1)") (class "Default")
      (node (ref "JP2") (pin "A5") (pinfunction "CC1_A5") (pintype "passive"))
      (node (ref "U4") (pin "11") (pinfunction "CC1_11") (pintype "bidirectional"))
    )
    (net (code "24") (name "Net-(JP2-CC2)") (class "Default")
      (node (ref "JP2") (pin "B5") (pinfunction "CC2_B5") (pintype "passive"))
      (node (ref "U4") (pin "12") (pinfunction "CC2_12") (pintype "bidirectional"))
    )
    (net (code "25") (name "Net-(JP6-Pad2)") (class "Default")
      (node (ref "JP6") (pin "2") (pinfunction "2_2") (pintype "passive"))
      (node (ref "R23") (pin "2") (pinfunction "2_2") (pintype "passive"))
    )
    (net (code "26") (name "Net-(JP6-Pad3)") (class "Default")
      (node (ref "JP6") (pin "3") (pinfunction "3_3") (pintype "passive"))
      (node (ref "R24") (pin "2") (pinfunction "2_2") (pintype "passive"))
    )
    (net (code "27") (name "Net-(LED1-PadA)") (class "Default")
      (node (ref "LED1") (pin "A") (pinfunction "A_A") (pintype "passive"))
      (node (ref "R5") (pin "2") (pinfunction "2_2") (pintype "passive"))
    )
    (net (code "28") (name "Net-(LED2-PadA)") (class "Default")
      (node (ref "LED2") (pin "A") (pinfunction "A_A") (pintype "passive"))
      (node (ref "R6") (pin "2") (pinfunction "2_2") (pintype "passive"))
    )
    (net (code "29") (name "Net-(Q1-D)") (class "Default")
      (node (ref "C1") (pin "1") (pinfunction "1_1") (pintype "passive"))
      (node (ref "C2") (pin "1") (pinfunction "1_1") (pintype "passive"))
      (node (ref "C3") (pin "1") (pinfunction "1_1") (pintype "passive"))
      (node (ref "C4") (pin "1") (pinfunction "1_1") (pintype "passive"))
      (node (ref "C5") (pin "1") (pinfunction "1_1") (pintype "passive"))
      (node (ref "D3") (pin "A") (pinfunction "A_A") (pintype "passive"))
      (node (ref "L1") (pin "2") (pinfunction "2_2") (pintype "passive"))
      (node (ref "Q1") (pin "2") (pinfunction "D_2") (pintype "passive"))
    )
    (net (code "30") (name "Net-(Q1-S-Pad3)") (class "Default")
      (node (ref "Q1") (pin "3") (pinfunction "S_3") (pintype "passive"))
      (node (ref "Q1") (pin "3B") (pinfunction "S_3B") (pintype "passive"))
      (node (ref "SJ1") (pin "2") (pinfunction "2_2") (pintype "bidirectional"))
    )
    (net (code "31") (name "Net-(Q2-G)") (class "Default")
      (node (ref "Q2") (pin "4") (pinfunction "G_4") (pintype "passive"))
      (node (ref "U3") (pin "1") (pinfunction "DGATE_1") (pintype "output"))
    )
    (net (code "32") (name "Net-(Q3-G)") (class "Default")
      (node (ref "Q3") (pin "4") (pinfunction "G_4") (pintype "passive"))
      (node (ref "R29") (pin "1") (pinfunction "1_1") (pintype "passive"))
      (node (ref "U3") (pin "8") (pinfunction "HGATE_8") (pintype "output"))
    )
    (net (code "33") (name "Net-(Q4A-G)") (class "Default")
      (node (ref "Q4") (pin "2") (pinfunction "G_2") (pintype "passive"))
      (node (ref "Q4") (pin "4") (pinfunction "G_4") (pintype "passive"))
      (node (ref "Q5") (pin "4") (pinfunction "G_4") (pintype "passive"))
      (node (ref "R9") (pin "1") (pinfunction "1_1") (pintype "passive"))
    )
    (net (code "34") (name "Net-(Q4A-S)") (class "Default")
      (node (ref "Q4") (pin "1") (pinfunction "S_1") (pintype "passive"))
      (node (ref "Q5") (pin "1") (pinfunction "S_1") (pintype "passive"))
      (node (ref "Q5") (pin "2") (pinfunction "S_2") (pintype "passive"))
      (node (ref "Q5") (pin "3") (pinfunction "S_3") (pintype "passive"))
      (node (ref "R11") (pin "1") (pinfunction "1_1") (pintype "passive"))
    )
    (net (code "35") (name "Net-(Q4B-S)") (class "Default")
      (node (ref "JP2") (pin "A9") (pinfunction "VBUS_A9") (pintype "passive"))
      (node (ref "JP2") (pin "B9") (pinfunction "VBUS_B9") (pintype "passive"))
      (node (ref "Q4") (pin "3") (pinfunction "S_3") (pintype "passive"))
      (node (ref "R8") (pin "1") (pinfunction "1_1") (pintype "passive"))
      (node (ref "TVS2") (pin "C") (pinfunction "2_C") (pintype "passive"))
      (node (ref "U4") (pin "1") (pinfunction "VCC2_1") (pintype "bidirectional"))
    )
    (net (code "36") (name "Net-(Q6-D)") (class "Default")
      (node (ref "Q6") (pin "3") (pinfunction "D_3") (pintype "passive"))
      (node (ref "R12") (pin "1") (pinfunction "1_1") (pintype "passive"))
      (node (ref "U3") (pin "6") (pinfunction "EN_UVLO_6") (pintype "passive"))
    )
    (net (code "37") (name "Net-(Q6-G)") (class "Default")
      (node (ref "Q6") (pin "1") (pinfunction "G_1") (pintype "passive"))
      (node (ref "R7") (pin "2") (pinfunction "2_2") (pintype "passive"))
      (node (ref "R8") (pin "2") (pinfunction "2_2") (pintype "passive"))
      (node (ref "TVS3") (pin "1") (pinfunction "2_1") (pintype "passive"))
    )
    (net (code "38") (name "Net-(Q7-D)") (class "Default")
      (node (ref "Q7") (pin "3") (pinfunction "D_3") (pintype "passive"))
      (node (ref "SJ6") (pin "1") (pinfunction "1_1") (pintype "passive"))
      (node (ref "SJ7") (pin "3") (pinfunction "3_3") (pintype "passive"))
    )
    (net (code "39") (name "Net-(Q7-G)") (class "Default")
      (node (ref "Q7") (pin "1") (pinfunction "G_1") (pintype "passive"))
      (node (ref "R27") (pin "1") (pinfunction "1_1") (pintype "passive"))
    )
    (net (code "40") (name "Net-(R10-Pad1)") (class "Default")
      (node (ref "R10") (pin "1") (pinfunction "1_1") (pintype "passive"))
      (node (ref "R11") (pin "2") (pinfunction "2_2") (pintype "passive"))
    )
    (net (code "41") (name "Net-(R13-Pad2)") (class "Default")
      (node (ref "R13") (pin "2") (pinfunction "2_2") (pintype "passive"))
      (node (ref "R14") (pin "1") (pinfunction "1_1") (pintype "passive"))
    )
    (net (code "42") (name "Net-(R15-Pad2)") (class "Default")
      (node (ref "R15") (pin "2") (pinfunction "2_2") (pintype "passive"))
      (node (ref "R16") (pin "1") (pinfunction "1_1") (pintype "passive"))
    )
    (net (code "43") (name "Net-(R17-Pad2)") (class "Default")
      (node (ref "R17") (pin "2") (pinfunction "2_2") (pintype "passive"))
      (node (ref "R18") (pin "1") (pinfunction "1_1") (pintype "passive"))
    )
    (net (code "44") (name "Net-(R19-Pad2)") (class "Default")
      (node (ref "R19") (pin "2") (pinfunction "2_2") (pintype "passive"))
      (node (ref "R20") (pin "1") (pinfunction "1_1") (pintype "passive"))
    )
    (net (code "45") (name "Net-(SW1B-P)") (class "Default")
      (node (ref "JP4") (pin "2") (pinfunction "2_2") (pintype "passive"))
      (node (ref "R25") (pin "2") (pinfunction "2_2") (pintype "passive"))
      (node (ref "SW1") (pin "C") (pinfunction "P_C") (pintype "passive"))
    )
    (net (code "46") (name "Net-(TVS1-2)") (class "Default")
      (node (ref "C20") (pin "1") (pinfunction "1_1") (pintype "passive"))
      (node (ref "JP3") (pin "P") (pinfunction "P_P") (pintype "bidirectional"))
      (node (ref "Q2") (pin "1") (pinfunction "S_1") (pintype "passive"))
      (node (ref "Q2") (pin "2") (pinfunction "S_2") (pintype "passive"))
      (node (ref "Q2") (pin "3") (pinfunction "S_3") (pintype "passive"))
      (node (ref "TVS1") (pin "C") (pinfunction "2_C") (pintype "passive"))
      (node (ref "U3") (pin "2") (pinfunction "A_2") (pintype "passive"))
      (node (ref "U3") (pin "3") (pinfunction "VSNS_3") (pintype "passive"))
    )
    (net (code "47") (name "Net-(U1-5V)") (class "Default")
      (node (ref "D2") (pin "C") (pinfunction "C_C") (pintype "passive"))
      (node (ref "U1") (pin "14") (pinfunction "5V_14") (pintype "power_in"))
    )
    (net (code "48") (name "Net-(U1-PA4_A1_D1)") (class "Default")
      (node (ref "R26") (pin "2") (pinfunction "2_2") (pintype "passive"))
      (node (ref "U1") (pin "2") (pinfunction "PA4_A1_D1_2") (pintype "bidirectional"))
    )
    (net (code "49") (name "Net-(U2-IN_P)") (class "Default")
      (node (ref "R1") (pin "2") (pinfunction "2_2") (pintype "passive"))
      (node (ref "R2") (pin "2") (pinfunction "2_2") (pintype "passive"))
      (node (ref "U2") (pin "6") (pinfunction "IN_P_6") (pintype "input"))
    )
    (net (code "50") (name "Net-(U2-OUT_SNK)") (class "Default")
      (node (ref "R4") (pin "1") (pinfunction "1_1") (pintype "passive"))
      (node (ref "U2") (pin "3") (pinfunction "OUT_SNK_3") (pintype "output"))
    )
    (net (code "51") (name "Net-(U2-OUT_SRC)") (class "Default")
      (node (ref "R3") (pin "1") (pinfunction "1_1") (pintype "passive"))
      (node (ref "U2") (pin "2") (pinfunction "OUT_SRC_2") (pintype "output"))
    )
    (net (code "52") (name "Net-(U3-CAP)") (class "Default")
      (node (ref "C21") (pin "1") (pinfunction "1_1") (pintype "passive"))
      (node (ref "U3") (pin "11") (pinfunction "CAP_11") (pintype "passive"))
    )
    (net (code "53") (name "Net-(U3-OV)") (class "Default")
      (node (ref "R30") (pin "1") (pinfunction "1_1") (pintype "passive"))
      (node (ref "R31") (pin "1") (pinfunction "1_1") (pintype "passive"))
      (node (ref "R32") (pin "1") (pinfunction "1_1") (pintype "passive"))
      (node (ref "U3") (pin "5") (pinfunction "OV_5") (pintype "passive"))
    )
    (net (code "54") (name "Net-(U3-SW)") (class "Default")
      (node (ref "R30") (pin "2") (pinfunction "2_2") (pintype "passive"))
      (node (ref "U3") (pin "4") (pinfunction "SW_4") (pintype "passive"))
    )
    (net (code "55") (name "Net-(U4-V5V)") (class "Default")
      (node (ref "C22") (pin "2") (pinfunction "2_2") (pintype "passive"))
      (node (ref "U4") (pin "13") (pinfunction "V5V_13") (pintype "bidirectional"))
    )
    (net (code "56") (name "Net-(U4-VCC1)") (class "Default")
      (node (ref "Q4") (pin "10") (pinfunction "D_10") (pintype "passive"))
      (node (ref "Q4") (pin "5") (pinfunction "D_5") (pintype "passive"))
      (node (ref "Q4") (pin "6") (pinfunction "D_6") (pintype "passive"))
      (node (ref "Q4") (pin "7") (pinfunction "D_7") (pintype "passive"))
      (node (ref "Q4") (pin "8") (pinfunction "D_8") (pintype "passive"))
      (node (ref "Q4") (pin "9") (pinfunction "D_9") (pintype "passive"))
      (node (ref "U4") (pin "16") (pinfunction "VCC1_16") (pintype "bidirectional"))
    )
    (net (code "57") (name "Net-(U4-VG_A)") (class "Default")
      (node (ref "R9") (pin "2") (pinfunction "2_2") (pintype "passive"))
      (node (ref "U4") (pin "15") (pinfunction "VG_A_15") (pintype "bidirectional"))
    )
    (net (code "58") (name "Net-(U4-VOUT)") (class "Default")
      (node (ref "R10") (pin "2") (pinfunction "2_2") (pintype "passive"))
      (node (ref "U4") (pin "14") (pinfunction "VOUT_14") (pintype "bidirectional"))
    )
    (net (code "59") (name "Net-(U4-VSEL)") (class "Default")
      (node (ref "R15") (pin "1") (pinfunction "1_1") (pintype "passive"))
      (node (ref "R17") (pin "1") (pinfunction "1_1") (pintype "passive"))
      (node (ref "R19") (pin "1") (pinfunction "1_1") (pintype "passive"))
      (node (ref "U4") (pin "4") (pinfunction "VSEL_4") (pintype "bidirectional"))
    )
    (net (code "60") (name "PWR-DIS") (class "Default")
      (node (ref "R25") (pin "1") (pinfunction "1_1") (pintype "passive"))
      (node (ref "TVS6") (pin "C") (pinfunction "2_C") (pintype "passive"))
      (node (ref "U1") (pin "8") (pinfunction "PB09_A7_D7_RX_8") (pintype "bidirectional"))
    )
    (net (code "61") (name "RF-GEN") (class "Default")
      (node (ref "R1") (pin "1") (pinfunction "1_1") (pintype "passive"))
      (node (ref "R26") (pin "1") (pinfunction "1_1") (pintype "passive"))
    )
    (net (code "62") (name "SEL2") (class "Default")
      (node (ref "R23") (pin "1") (pinfunction "1_1") (pintype "passive"))
      (node (ref "TVS4") (pin "C") (pinfunction "2_C") (pintype "passive"))
      (node (ref "U1") (pin "6") (pinfunction "PA9_A5_D5_SCL_6") (pintype "bidirectional"))
    )
    (net (code "63") (name "SEL3") (class "Default")
      (node (ref "R24") (pin "1") (pinfunction "1_1") (pintype "passive"))
      (node (ref "TVS5") (pin "C") (pinfunction "2_C") (pintype "passive"))
      (node (ref "U1") (pin "4") (pinfunction "PA11_A3_D3_4") (pintype "bidirectional"))
    )
    (net (code "64") (name "USB-I-SEL") (class "Default")
      (node (ref "JP5") (pin "1") (pinfunction "1_1") (pintype "passive"))
      (node (ref "R13") (pin "1") (pinfunction "1_1") (pintype "passive"))
      (node (ref "U4") (pin "5") (pinfunction "ISEL_5") (pintype "bidirectional"))
    )
    (net (code "65") (name "USB-V-SEL-20V") (class "Default")
      (node (ref "JP5") (pin "6") (pinfunction "6_6") (pintype "passive"))
      (node (ref "R18") (pin "2") (pinfunction "2_2") (pintype "passive"))
    )
    (net (code "66") (name "USB-V-SEL-28V") (class "Default")
      (node (ref "JP5") (pin "4") (pinfunction "4_4") (pintype "passive"))
      (node (ref "R20") (pin "2") (pinfunction "2_2") (pintype "passive"))
    )
    (net (code "67") (name "VCD") (class "Default")
      (node (ref "C21") (pin "2") (pinfunction "2_2") (pintype "passive"))
      (node (ref "C24") (pin "1") (pinfunction "1_1") (pintype "passive"))
      (node (ref "Q2") (pin "5") (pinfunction "D_5") (pintype "passive"))
      (node (ref "Q2") (pin "6") (pinfunction "D_6") (pintype "passive"))
      (node (ref "Q2") (pin "7") (pinfunction "D_7") (pintype "passive"))
      (node (ref "Q2") (pin "8") (pinfunction "D_8") (pintype "passive"))
      (node (ref "Q2") (pin "9") (pinfunction "D_9") (pintype "passive"))
      (node (ref "Q3") (pin "5") (pinfunction "D_5") (pintype "passive"))
      (node (ref "Q3") (pin "6") (pinfunction "D_6") (pintype "passive"))
      (node (ref "Q3") (pin "7") (pinfunction "D_7") (pintype "passive"))
      (node (ref "Q3") (pin "8") (pinfunction "D_8") (pintype "passive"))
      (node (ref "Q3") (pin "9") (pinfunction "D_9") (pintype "passive"))
      (node (ref "R12") (pin "2") (pinfunction "2_2") (pintype "passive"))
      (node (ref "U3") (pin "10") (pinfunction "VS_10") (pintype "power_in"))
      (node (ref "U3") (pin "12") (pinfunction "C_12") (pintype "passive"))
    )
    (net (code "68") (name "unconnected-(FAN1-PadT)") (class "Default")
      (node (ref "FAN1") (pin "T") (pinfunction "T_T") (pintype "bidirectional"))
    )
    (net (code "69") (name "unconnected-(SW1B-O-PadL)") (class "Default")
      (node (ref "SW1") (pin "L") (pinfunction "O_L") (pintype "passive"))
    )
    (net (code "70") (name "unconnected-(U1-PA02_A0_D0-Pad1)") (class "Default")
      (node (ref "U1") (pin "1") (pinfunction "PA02_A0_D0_1") (pintype "bidirectional"))
    )
    (net (code "71") (name "unconnected-(U1-PA5_A9_D9_MISO-Pad10)") (class "Default")
      (node (ref "U1") (pin "10") (pinfunction "PA5_A9_D9_MISO_10") (pintype "bidirectional"))
    )
    (net (code "72") (name "unconnected-(U1-PA8_A4_D4_SDA-Pad5)") (class "Default")
      (node (ref "U1") (pin "5") (pinfunction "PA8_A4_D4_SDA_5") (pintype "bidirectional"))
    )
    (net (code "73") (name "unconnected-(U3-RTN-Pad13)") (class "Default")
      (node (ref "U3") (pin "13") (pinfunction "RTN_13") (pintype "passive"))
    )
    (net (code "74") (name "unconnected-(U4-DN-Pad10)") (class "Default")
      (node (ref "U4") (pin "10") (pinfunction "DN_10") (pintype "bidirectional"))
    )
    (net (code "75") (name "unconnected-(U4-DP-Pad9)") (class "Default")
      (node (ref "U4") (pin "9") (pinfunction "DP_9") (pintype "bidirectional"))
    )
    (net (code "76") (name "unconnected-(U4-GPIO-Pad6)") (class "Default")
      (node (ref "U4") (pin "6") (pinfunction "GPIO_6") (pintype "bidirectional"))
    )
    (net (code "77") (name "unconnected-(U4-VFB-Pad7)") (class "Default")
      (node (ref "U4") (pin "7") (pinfunction "VFB_7") (pintype "bidirectional"))
    )
  )
)
